# Supply.net
KiCad netlist of a schematic drawn in Altium Designer
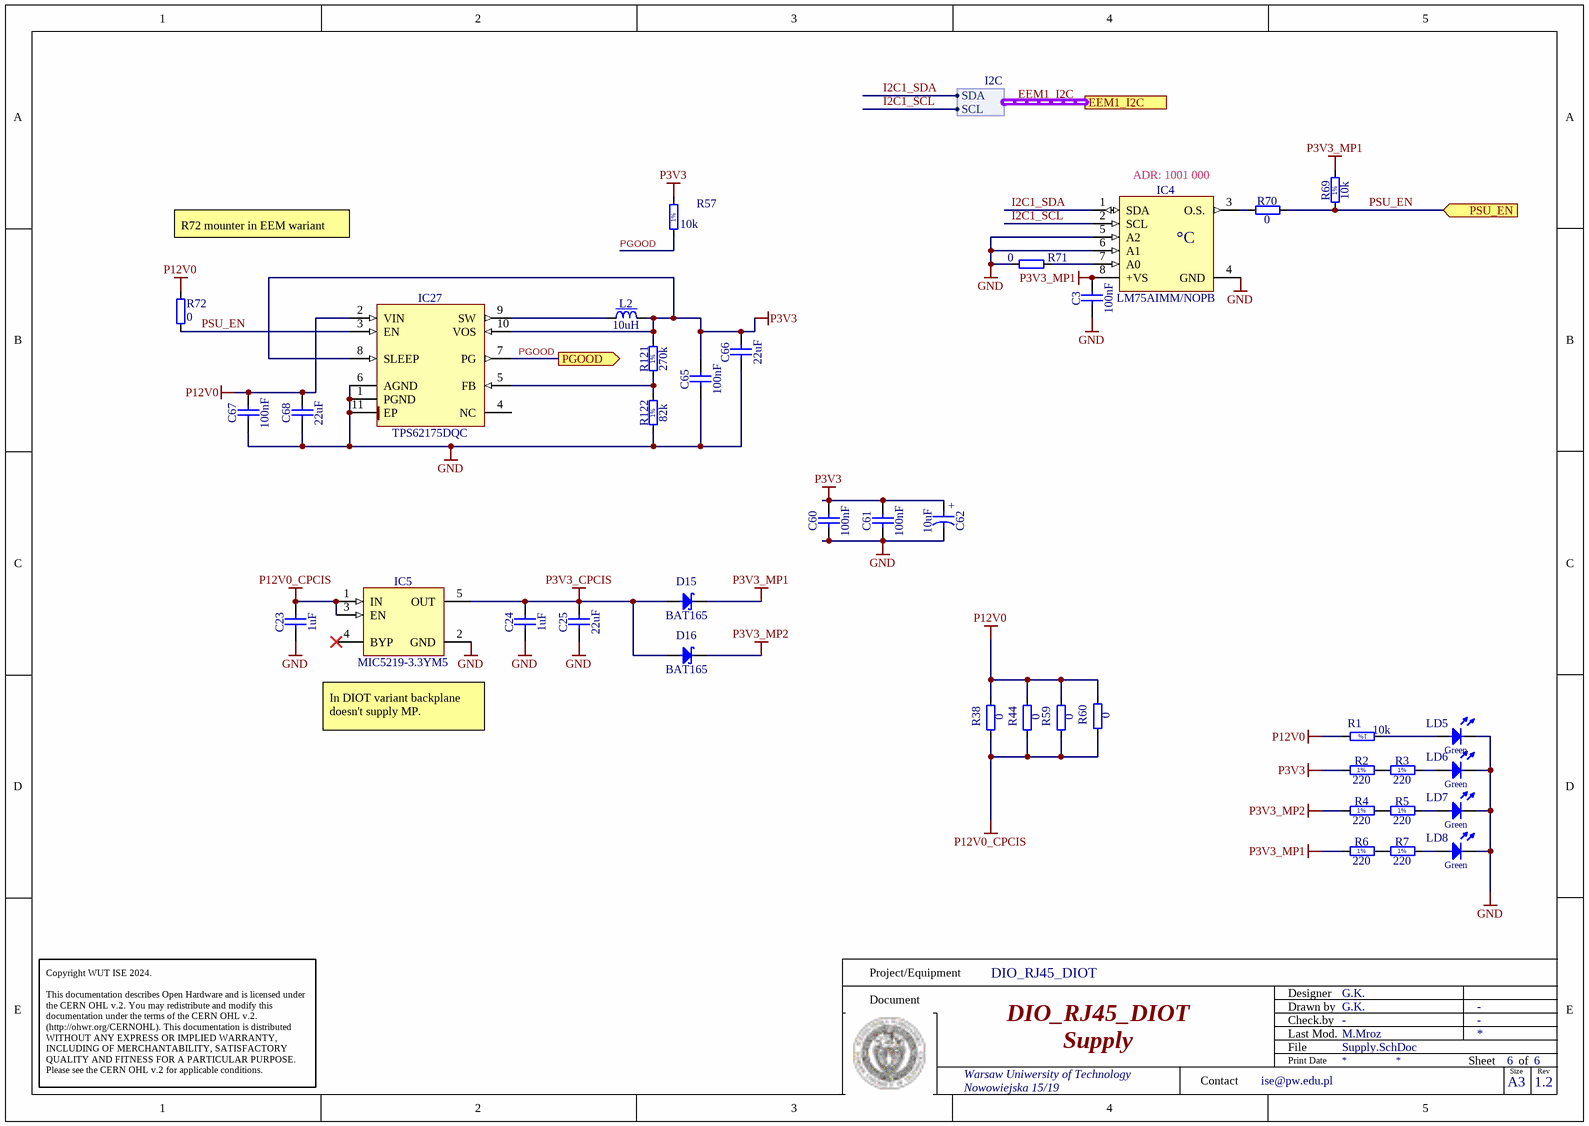
[diagram p0: Supply.SchDoc]

(export (version "E")
  (design (tool "Eeschema 10.0.6"))
  (components
    (comp (ref "C3")
      (value "100nF")
      (footprint "CAPC1005X55N")
      (description "Non-polarised capacitor")
      (fields
        (field (name "PART NUMBER") "CC0402_100NF_16V_10%_X5R")
        (field (name "VOLTAGE") "16V")
        (field (name "AUTHOR") "CERN DEM JLC")
      )
      (libsource (lib "Capacitors") (part "Capacitor - non polarized"))
    )
    (comp (ref "C23")
      (value "1uF")
      (footprint "CAPC1608X87N")
      (description "Non-polarised capacitor")
      (fields
        (field (name "PART NUMBER") "CC0603_1UF_25V_10%_X7R")
        (field (name "VOLTAGE") "25V")
        (field (name "AUTHOR") "CERN DEM JLC")
      )
      (libsource (lib "Capacitors") (part "Capacitor - non polarized"))
    )
    (comp (ref "C24")
      (value "1uF")
      (footprint "CAPC1608X87N")
      (description "Non-polarised capacitor")
      (fields
        (field (name "PART NUMBER") "CC0603_1UF_25V_10%_X7R")
        (field (name "VOLTAGE") "25V")
        (field (name "AUTHOR") "CERN DEM JLC")
      )
      (libsource (lib "Capacitors") (part "Capacitor - non polarized"))
    )
    (comp (ref "C25")
      (value "22uF")
      (footprint "CAPC2012X135N")
      (description "Non-polarised capacitor")
      (fields
        (field (name "PART NUMBER") "CC0805_22UF_16V_10%_X5R")
        (field (name "VOLTAGE") "16V")
        (field (name "AUTHOR") "CERN DEM JLC")
      )
      (libsource (lib "Capacitors") (part "Capacitor - non polarized"))
    )
    (comp (ref "C60")
      (value "100nF")
      (footprint "CAPC1005X55N")
      (description "Non-polarised capacitor")
      (fields
        (field (name "PART NUMBER") "CC0402_100NF_16V_10%_X5R")
        (field (name "VOLTAGE") "16V")
        (field (name "AUTHOR") "CERN DEM JLC")
      )
      (libsource (lib "Capacitors") (part "Capacitor - non polarized"))
    )
    (comp (ref "C61")
      (value "100nF")
      (footprint "CAPC1005X55N")
      (description "Non-polarised capacitor")
      (fields
        (field (name "PART NUMBER") "CC0402_100NF_16V_10%_X5R")
        (field (name "VOLTAGE") "16V")
        (field (name "AUTHOR") "CERN DEM JLC")
      )
      (libsource (lib "Capacitors") (part "Capacitor - non polarized"))
    )
    (comp (ref "C62")
      (value "10uF")
      (footprint "CAPAE430X540N")
      (description "Polarised capacitor")
      (fields
        (field (name "PART NUMBER") "CAE430-540_10UF_16V_20%")
        (field (name "VOLTAGE") "16V")
        (field (name "AUTHOR") "CERN DEM JLC")
      )
      (libsource (lib "Capacitors") (part "Capacitor - polarized"))
    )
    (comp (ref "C65")
      (value "100nF")
      (footprint "CAPC1005X55N")
      (description "Non-polarised capacitor")
      (fields
        (field (name "PART NUMBER") "CC0402_100NF_16V_10%_X5R")
        (field (name "VOLTAGE") "16V")
        (field (name "AUTHOR") "CERN DEM JLC")
      )
      (libsource (lib "Capacitors") (part "Capacitor - non polarized"))
    )
    (comp (ref "C66")
      (value "22uF")
      (footprint "CAPC2012X135N")
      (description "Non-polarised capacitor")
      (fields
        (field (name "PART NUMBER") "CC0805_22UF_16V_10%_X5R")
        (field (name "VOLTAGE") "16V")
        (field (name "AUTHOR") "CERN DEM JLC")
      )
      (libsource (lib "Capacitors") (part "Capacitor - non polarized"))
    )
    (comp (ref "C67")
      (value "100nF")
      (footprint "CAPC1005X55N")
      (description "Non-polarised capacitor")
      (fields
        (field (name "PART NUMBER") "CC0402_100NF_16V_10%_X5R")
        (field (name "VOLTAGE") "16V")
        (field (name "AUTHOR") "CERN DEM JLC")
      )
      (libsource (lib "Capacitors") (part "Capacitor - non polarized"))
    )
    (comp (ref "C68")
      (value "22uF")
      (footprint "CAPC2012X135N")
      (description "Non-polarised capacitor")
      (fields
        (field (name "PART NUMBER") "CC0805_22UF_16V_10%_X5R")
        (field (name "VOLTAGE") "16V")
        (field (name "AUTHOR") "CERN DEM JLC")
      )
      (libsource (lib "Capacitors") (part "Capacitor - non polarized"))
    )
    (comp (ref "D15")
      (value "BAT165")
      (footprint "SOD2512X110N")
      (description "Schottky Diode")
      (fields
        (field (name "MANUFACTURER") "INFINEON")
        (field (name "VOLTAGE") "40V")
        (field (name "AUTHOR") "CERN DEM JLC")
      )
      (libsource (lib "ICs And Semiconductors") (part "Diode Schottky"))
    )
    (comp (ref "D16")
      (value "BAT165")
      (footprint "SOD2512X110N")
      (description "Schottky Diode")
      (fields
        (field (name "MANUFACTURER") "INFINEON")
        (field (name "VOLTAGE") "40V")
        (field (name "AUTHOR") "CERN DEM JLC")
      )
      (libsource (lib "ICs And Semiconductors") (part "Diode Schottky"))
    )
    (comp (ref "IC4")
      (value "LM75AIMM/NOPB")
      (footprint "SOP65P490X109-8N")
      (description "Digital Temperature Sensor and Thermal Watchdog with Two-Wire Interface")
      (fields (field (name "MANUFACTURER") "TEXAS INSTRUMENTS") (field (name "AUTHOR") "CERN DEM JLC"))
      (libsource (lib "ICs And Semiconductors") (part "LM75"))
    )
    (comp (ref "IC5")
      (value "MIC5219-3.3YM5")
      (footprint "SOT95P280X145-5N")
      (description "500mA Peak Output LDO Regulator")
      (fields (field (name "MANUFACTURER") "MICROCHIP TECHNOLOGY") (field (name "AUTHOR") "CERN DEM WB"))
      (libsource (lib "ICs And Semiconductors") (part "MIC5219-X.XYM5"))
    )
    (comp (ref "IC27")
      (value "TPS62175DQC")
      (footprint "SON50P200X300X80-11N-R94X250")
      (description "4.75-28VDC to 1-6VDC, 500mA Step-Down Converter With Sleep Mode")
      (fields (field (name "MANUFACTURER") "TEXAS INSTRUMENTS") (field (name "AUTHOR") "CERN DEM JMW"))
      (libsource (lib "ICs And Semiconductors") (part "TPS62175"))
    )
    (comp (ref "L2")
      (value "10uH")
      (footprint "IND_MURATA-PS_8400")
      (description "Inductor With Core")
      (fields
        (field (name "PART NUMBER") "IND_10UH_10%_MURATA-PS_8400")
        (field (name "POWER") "950mA")
        (field (name "AUTHOR") "CERN DEM JLC")
      )
      (libsource (lib "Inductors & Transformers") (part "Inductor With Magnetic core"))
    )
    (comp (ref "LD5")
      (value "Green")
      (footprint "LED_KINGBRIGHT_KPH-1608CGCK")
      (description "LED Green 1C 2A")
      (fields
        (field (name "PART NUMBER") "LED_KINGBRIGHT_KPH-1608CGCK")
        (field (name "MANUFACTURER") "KINGBRIGHT")
        (field (name "AUTHOR") "CERN DEM JLC")
      )
      (libsource (lib "ICs And Semiconductors") (part "LED Green 1C 2A"))
    )
    (comp (ref "LD6")
      (value "Green")
      (footprint "LED_KINGBRIGHT_KPH-1608CGCK")
      (description "LED Green 1C 2A")
      (fields
        (field (name "PART NUMBER") "LED_KINGBRIGHT_KPH-1608CGCK")
        (field (name "MANUFACTURER") "KINGBRIGHT")
        (field (name "AUTHOR") "CERN DEM JLC")
      )
      (libsource (lib "ICs And Semiconductors") (part "LED Green 1C 2A"))
    )
    (comp (ref "LD7")
      (value "Green")
      (footprint "LED_KINGBRIGHT_KPH-1608CGCK")
      (description "LED Green 1C 2A")
      (fields
        (field (name "PART NUMBER") "LED_KINGBRIGHT_KPH-1608CGCK")
        (field (name "MANUFACTURER") "KINGBRIGHT")
        (field (name "AUTHOR") "CERN DEM JLC")
      )
      (libsource (lib "ICs And Semiconductors") (part "LED Green 1C 2A"))
    )
    (comp (ref "LD8")
      (value "Green")
      (footprint "LED_KINGBRIGHT_KPH-1608CGCK")
      (description "LED Green 1C 2A")
      (fields
        (field (name "PART NUMBER") "LED_KINGBRIGHT_KPH-1608CGCK")
        (field (name "MANUFACTURER") "KINGBRIGHT")
        (field (name "AUTHOR") "CERN DEM JLC")
      )
      (libsource (lib "ICs And Semiconductors") (part "LED Green 1C 2A"))
    )
    (comp (ref "R1")
      (value "10k")
      (footprint "RESC1005X40N")
      (description "Resistor - 1%")
      (fields
        (field (name "PART NUMBER") "R0402_10K_1%_0.0625W_100PPM")
        (field (name "POWER") "0.0625W")
        (field (name "AUTHOR") "CERN DEM JLC")
      )
      (libsource (lib "Resistors") (part "Resistor - 1%"))
    )
    (comp (ref "R2")
      (value "220")
      (footprint "RESC1608X55N")
      (description "Resistor - 1%")
      (fields
        (field (name "PART NUMBER") "R0603_220R_1%_0.1W_100PPM")
        (field (name "POWER") "0.1W")
        (field (name "AUTHOR") "CERN DEM JLC")
      )
      (libsource (lib "Resistors") (part "Resistor - 1%"))
    )
    (comp (ref "R3")
      (value "220")
      (footprint "RESC1608X55N")
      (description "Resistor - 1%")
      (fields
        (field (name "PART NUMBER") "R0603_220R_1%_0.1W_100PPM")
        (field (name "POWER") "0.1W")
        (field (name "AUTHOR") "CERN DEM JLC")
      )
      (libsource (lib "Resistors") (part "Resistor - 1%"))
    )
    (comp (ref "R4")
      (value "220")
      (footprint "RESC1608X55N")
      (description "Resistor - 1%")
      (fields
        (field (name "PART NUMBER") "R0603_220R_1%_0.1W_100PPM")
        (field (name "POWER") "0.1W")
        (field (name "AUTHOR") "CERN DEM JLC")
      )
      (libsource (lib "Resistors") (part "Resistor - 1%"))
    )
    (comp (ref "R5")
      (value "220")
      (footprint "RESC1608X55N")
      (description "Resistor - 1%")
      (fields
        (field (name "PART NUMBER") "R0603_220R_1%_0.1W_100PPM")
        (field (name "POWER") "0.1W")
        (field (name "AUTHOR") "CERN DEM JLC")
      )
      (libsource (lib "Resistors") (part "Resistor - 1%"))
    )
    (comp (ref "R6")
      (value "220")
      (footprint "RESC1608X55N")
      (description "Resistor - 1%")
      (fields
        (field (name "PART NUMBER") "R0603_220R_1%_0.1W_100PPM")
        (field (name "POWER") "0.1W")
        (field (name "AUTHOR") "CERN DEM JLC")
      )
      (libsource (lib "Resistors") (part "Resistor - 1%"))
    )
    (comp (ref "R7")
      (value "220")
      (footprint "RESC1608X55N")
      (description "Resistor - 1%")
      (fields
        (field (name "PART NUMBER") "R0603_220R_1%_0.1W_100PPM")
        (field (name "POWER") "0.1W")
        (field (name "AUTHOR") "CERN DEM JLC")
      )
      (libsource (lib "Resistors") (part "Resistor - 1%"))
    )
    (comp (ref "R38")
      (value "0")
      (footprint "RESC1005X35N")
      (description "Resistor")
      (fields
        (field (name "PART NUMBER") "R0603_0R_JUMPER")
        (field (name "MANUFACTURER") "GENERIC")
        (field (name "AUTHOR") "CERN DEM JLC")
      )
      (libsource (lib "Resistors") (part "Resistor"))
    )
    (comp (ref "R44")
      (value "0")
      (footprint "RESC1005X35N")
      (description "Resistor")
      (fields
        (field (name "PART NUMBER") "R0603_0R_JUMPER")
        (field (name "MANUFACTURER") "GENERIC")
        (field (name "AUTHOR") "CERN DEM JLC")
      )
      (libsource (lib "Resistors") (part "Resistor"))
    )
    (comp (ref "R57")
      (value "10k")
      (footprint "RESC1005X40N")
      (description "Resistor - 1%")
      (fields
        (field (name "PART NUMBER") "R0402_10K_1%_0.0625W_100PPM")
        (field (name "POWER") "0.0625W")
        (field (name "AUTHOR") "CERN DEM JLC")
      )
      (libsource (lib "Resistors") (part "Resistor - 1%"))
    )
    (comp (ref "R59")
      (value "0")
      (footprint "RESC1005X35N")
      (description "Resistor")
      (fields
        (field (name "PART NUMBER") "R0603_0R_JUMPER")
        (field (name "MANUFACTURER") "GENERIC")
        (field (name "AUTHOR") "CERN DEM JLC")
      )
      (libsource (lib "Resistors") (part "Resistor"))
    )
    (comp (ref "R60")
      (value "0")
      (footprint "RESC1005X35N")
      (description "Resistor")
      (fields
        (field (name "PART NUMBER") "R0603_0R_JUMPER")
        (field (name "MANUFACTURER") "GENERIC")
        (field (name "AUTHOR") "CERN DEM JLC")
      )
      (libsource (lib "Resistors") (part "Resistor"))
    )
    (comp (ref "R69")
      (value "10k")
      (footprint "RESC1005X40N")
      (description "Resistor - 1%")
      (fields
        (field (name "PART NUMBER") "R0402_10K_1%_0.0625W_100PPM")
        (field (name "POWER") "0.0625W")
        (field (name "AUTHOR") "CERN DEM JLC")
      )
      (libsource (lib "Resistors") (part "Resistor - 1%"))
    )
    (comp (ref "R70")
      (value "0")
      (footprint "RESC1005X35N")
      (description "Resistor")
      (fields
        (field (name "PART NUMBER") "R0402_0R_JUMPER")
        (field (name "MANUFACTURER") "GENERIC")
        (field (name "AUTHOR") "CERN DEM JLC")
      )
      (libsource (lib "Resistors") (part "Resistor"))
    )
    (comp (ref "R71")
      (value "0")
      (footprint "RESC1005X35N")
      (description "Resistor")
      (fields
        (field (name "PART NUMBER") "R0402_0R_JUMPER")
        (field (name "MANUFACTURER") "GENERIC")
        (field (name "AUTHOR") "CERN DEM JLC")
      )
      (libsource (lib "Resistors") (part "Resistor"))
    )
    (comp (ref "R72")
      (value "0")
      (footprint "RESC1005X35N")
      (description "Resistor")
      (fields
        (field (name "PART NUMBER") "R0402_0R_JUMPER")
        (field (name "MANUFACTURER") "GENERIC")
        (field (name "AUTHOR") "CERN DEM JLC")
      )
      (libsource (lib "Resistors") (part "Resistor"))
    )
    (comp (ref "R121")
      (value "270k")
      (footprint "RESC1608X55N")
      (description "Resistor - 1%")
      (fields
        (field (name "PART NUMBER") "R0603_270K_1%_0.1W_100PPM")
        (field (name "POWER") "0.1W")
        (field (name "AUTHOR") "CERN DEM JLC")
      )
      (libsource (lib "Resistors") (part "Resistor - 1%"))
    )
    (comp (ref "R122")
      (value "82k")
      (footprint "RESC1608X55N")
      (description "Resistor - 1%")
      (fields
        (field (name "PART NUMBER") "R0603_82K_1%_0.1W_100PPM")
        (field (name "POWER") "0.1W")
        (field (name "AUTHOR") "CERN DEM JLC")
      )
      (libsource (lib "Resistors") (part "Resistor - 1%"))
    )
  )
  (nets
    (net (code "3") (name "/I2C1_SCL") (class "Default")
      (node (ref "IC4") (pin "2") (pinfunction "SCL_2") (pintype "input"))
    )
    (net (code "4") (name "/I2C1_SDA") (class "Default")
      (node (ref "IC4") (pin "1") (pinfunction "SDA_1") (pintype "bidirectional"))
    )
    (net (code "5") (name "/PGOOD") (class "Default")
      (node (ref "IC27") (pin "7") (pinfunction "PG_7") (pintype "output"))
      (node (ref "R57") (pin "1") (pinfunction "1_1") (pintype "passive"))
    )
    (net (code "6") (name "/PSU_EN") (class "Default")
      (node (ref "IC27") (pin "3") (pinfunction "EN_3") (pintype "input"))
      (node (ref "R69") (pin "1") (pinfunction "1_1") (pintype "passive"))
      (node (ref "R70") (pin "2") (pinfunction "2_2") (pintype "passive"))
      (node (ref "R72") (pin "1") (pinfunction "1_1") (pintype "passive"))
    )
    (net (code "7") (name "GND") (class "Default")
      (node (ref "C23") (pin "1") (pinfunction "1_1") (pintype "passive"))
      (node (ref "C24") (pin "1") (pinfunction "1_1") (pintype "passive"))
      (node (ref "C25") (pin "1") (pinfunction "1_1") (pintype "passive"))
      (node (ref "C3") (pin "1") (pinfunction "1_1") (pintype "passive"))
      (node (ref "C60") (pin "1") (pinfunction "1_1") (pintype "passive"))
      (node (ref "C61") (pin "1") (pinfunction "1_1") (pintype "passive"))
      (node (ref "C62") (pin "2") (pinfunction "2_2") (pintype "passive"))
      (node (ref "C65") (pin "1") (pinfunction "1_1") (pintype "passive"))
      (node (ref "C66") (pin "1") (pinfunction "1_1") (pintype "passive"))
      (node (ref "C67") (pin "1") (pinfunction "1_1") (pintype "passive"))
      (node (ref "C68") (pin "1") (pinfunction "1_1") (pintype "passive"))
      (node (ref "IC27") (pin "1") (pinfunction "PGND_1") (pintype "power_in"))
      (node (ref "IC27") (pin "11") (pinfunction "EP_11") (pintype "power_in"))
      (node (ref "IC27") (pin "6") (pinfunction "AGND_6") (pintype "power_in"))
      (node (ref "IC4") (pin "4") (pinfunction "GND_4") (pintype "power_in"))
      (node (ref "IC4") (pin "5") (pinfunction "A2_5") (pintype "input"))
      (node (ref "IC4") (pin "6") (pinfunction "A1_6") (pintype "input"))
      (node (ref "IC5") (pin "2") (pinfunction "GND_2") (pintype "power_in"))
      (node (ref "LD5") (pin "1") (pinfunction "C_1") (pintype "passive"))
      (node (ref "LD6") (pin "1") (pinfunction "C_1") (pintype "passive"))
      (node (ref "LD7") (pin "1") (pinfunction "C_1") (pintype "passive"))
      (node (ref "LD8") (pin "1") (pinfunction "C_1") (pintype "passive"))
      (node (ref "R122") (pin "1") (pinfunction "1_1") (pintype "passive"))
      (node (ref "R71") (pin "1") (pinfunction "1_1") (pintype "passive"))
    )
    (net (code "8") (name "Net-(IC4-A0)") (class "Default")
      (node (ref "IC4") (pin "7") (pinfunction "A0_7") (pintype "input"))
      (node (ref "R71") (pin "2") (pinfunction "2_2") (pintype "passive"))
    )
    (net (code "9") (name "Net-(IC4-O.S.)") (class "Default")
      (node (ref "IC4") (pin "3") (pinfunction "O.S._3") (pintype "output"))
      (node (ref "R70") (pin "1") (pinfunction "1_1") (pintype "passive"))
    )
    (net (code "10") (name "Net-(IC27-FB)") (class "Default")
      (node (ref "IC27") (pin "5") (pinfunction "FB_5") (pintype "input"))
      (node (ref "R121") (pin "1") (pinfunction "1_1") (pintype "passive"))
      (node (ref "R122") (pin "2") (pinfunction "2_2") (pintype "passive"))
    )
    (net (code "11") (name "Net-(IC27-SW)") (class "Default")
      (node (ref "IC27") (pin "9") (pinfunction "SW_9") (pintype "output"))
      (node (ref "L2") (pin "1") (pinfunction "1_1") (pintype "passive"))
    )
    (net (code "12") (name "Net-(LD5-A)") (class "Default")
      (node (ref "LD5") (pin "2") (pinfunction "A_2") (pintype "passive"))
      (node (ref "R1") (pin "1") (pinfunction "1_1") (pintype "passive"))
    )
    (net (code "13") (name "Net-(LD6-A)") (class "Default")
      (node (ref "LD6") (pin "2") (pinfunction "A_2") (pintype "passive"))
      (node (ref "R3") (pin "2") (pinfunction "2_2") (pintype "passive"))
    )
    (net (code "14") (name "Net-(LD7-A)") (class "Default")
      (node (ref "LD7") (pin "2") (pinfunction "A_2") (pintype "passive"))
      (node (ref "R5") (pin "2") (pinfunction "2_2") (pintype "passive"))
    )
    (net (code "15") (name "Net-(LD8-A)") (class "Default")
      (node (ref "LD8") (pin "2") (pinfunction "A_2") (pintype "passive"))
      (node (ref "R7") (pin "2") (pinfunction "2_2") (pintype "passive"))
    )
    (net (code "16") (name "Net-(R2-Pad2)") (class "Default")
      (node (ref "R2") (pin "2") (pinfunction "2_2") (pintype "passive"))
      (node (ref "R3") (pin "1") (pinfunction "1_1") (pintype "passive"))
    )
    (net (code "17") (name "Net-(R4-Pad2)") (class "Default")
      (node (ref "R4") (pin "2") (pinfunction "2_2") (pintype "passive"))
      (node (ref "R5") (pin "1") (pinfunction "1_1") (pintype "passive"))
    )
    (net (code "18") (name "Net-(R6-Pad2)") (class "Default")
      (node (ref "R6") (pin "2") (pinfunction "2_2") (pintype "passive"))
      (node (ref "R7") (pin "1") (pinfunction "1_1") (pintype "passive"))
    )
    (net (code "19") (name "P3V3") (class "Default")
      (node (ref "C60") (pin "2") (pinfunction "2_2") (pintype "passive"))
      (node (ref "C61") (pin "2") (pinfunction "2_2") (pintype "passive"))
      (node (ref "C62") (pin "1") (pinfunction "1_1") (pintype "passive"))
      (node (ref "C65") (pin "2") (pinfunction "2_2") (pintype "passive"))
      (node (ref "C66") (pin "2") (pinfunction "2_2") (pintype "passive"))
      (node (ref "IC27") (pin "10") (pinfunction "VOS_10") (pintype "input"))
      (node (ref "IC27") (pin "8") (pinfunction "SLEEP_8") (pintype "input"))
      (node (ref "L2") (pin "2") (pinfunction "2_2") (pintype "passive"))
      (node (ref "R121") (pin "2") (pinfunction "2_2") (pintype "passive"))
      (node (ref "R2") (pin "1") (pinfunction "1_1") (pintype "passive"))
      (node (ref "R57") (pin "2") (pinfunction "2_2") (pintype "passive"))
    )
    (net (code "20") (name "P3V3_CPCIS") (class "Default")
      (node (ref "C24") (pin "2") (pinfunction "2_2") (pintype "passive"))
      (node (ref "C25") (pin "2") (pinfunction "2_2") (pintype "passive"))
      (node (ref "D15") (pin "2") (pinfunction "A_2") (pintype "passive"))
      (node (ref "D16") (pin "2") (pinfunction "A_2") (pintype "passive"))
      (node (ref "IC5") (pin "5") (pinfunction "OUT_5") (pintype "power_in"))
    )
    (net (code "21") (name "P3V3_MP1") (class "Default")
      (node (ref "C3") (pin "2") (pinfunction "2_2") (pintype "passive"))
      (node (ref "D15") (pin "1") (pinfunction "C_1") (pintype "passive"))
      (node (ref "IC4") (pin "8") (pinfunction "+VS_8") (pintype "power_in"))
      (node (ref "R6") (pin "1") (pinfunction "1_1") (pintype "passive"))
      (node (ref "R69") (pin "2") (pinfunction "2_2") (pintype "passive"))
    )
    (net (code "22") (name "P3V3_MP2") (class "Default")
      (node (ref "D16") (pin "1") (pinfunction "C_1") (pintype "passive"))
      (node (ref "R4") (pin "1") (pinfunction "1_1") (pintype "passive"))
    )
    (net (code "23") (name "P12V0") (class "Default")
      (node (ref "C67") (pin "2") (pinfunction "2_2") (pintype "passive"))
      (node (ref "C68") (pin "2") (pinfunction "2_2") (pintype "passive"))
      (node (ref "IC27") (pin "2") (pinfunction "VIN_2") (pintype "input"))
      (node (ref "R1") (pin "2") (pinfunction "2_2") (pintype "passive"))
      (node (ref "R38") (pin "1") (pinfunction "1_1") (pintype "passive"))
      (node (ref "R44") (pin "1") (pinfunction "1_1") (pintype "passive"))
      (node (ref "R59") (pin "1") (pinfunction "1_1") (pintype "passive"))
      (node (ref "R60") (pin "1") (pinfunction "1_1") (pintype "passive"))
      (node (ref "R72") (pin "2") (pinfunction "2_2") (pintype "passive"))
    )
    (net (code "24") (name "P12V0_CPCIS") (class "Default")
      (node (ref "C23") (pin "2") (pinfunction "2_2") (pintype "passive"))
      (node (ref "IC5") (pin "1") (pinfunction "IN_1") (pintype "input"))
      (node (ref "IC5") (pin "3") (pinfunction "EN_3") (pintype "input"))
      (node (ref "R38") (pin "2") (pinfunction "2_2") (pintype "passive"))
      (node (ref "R44") (pin "2") (pinfunction "2_2") (pintype "passive"))
      (node (ref "R59") (pin "2") (pinfunction "2_2") (pintype "passive"))
      (node (ref "R60") (pin "2") (pinfunction "2_2") (pintype "passive"))
    )
    (net (code "25") (name "unconnected-(IC5-BYP-Pad4)") (class "Default")
      (node (ref "IC5") (pin "4") (pinfunction "BYP_4") (pintype "passive+no_connect"))
    )
    (net (code "26") (name "unconnected-(IC27-NC-Pad4)") (class "Default")
      (node (ref "IC27") (pin "4") (pinfunction "NC_4") (pintype "passive"))
    )
  )
)
